# Power_Bank_Circuit.net
KiCad netlist of a schematic drawn in Altium Designer
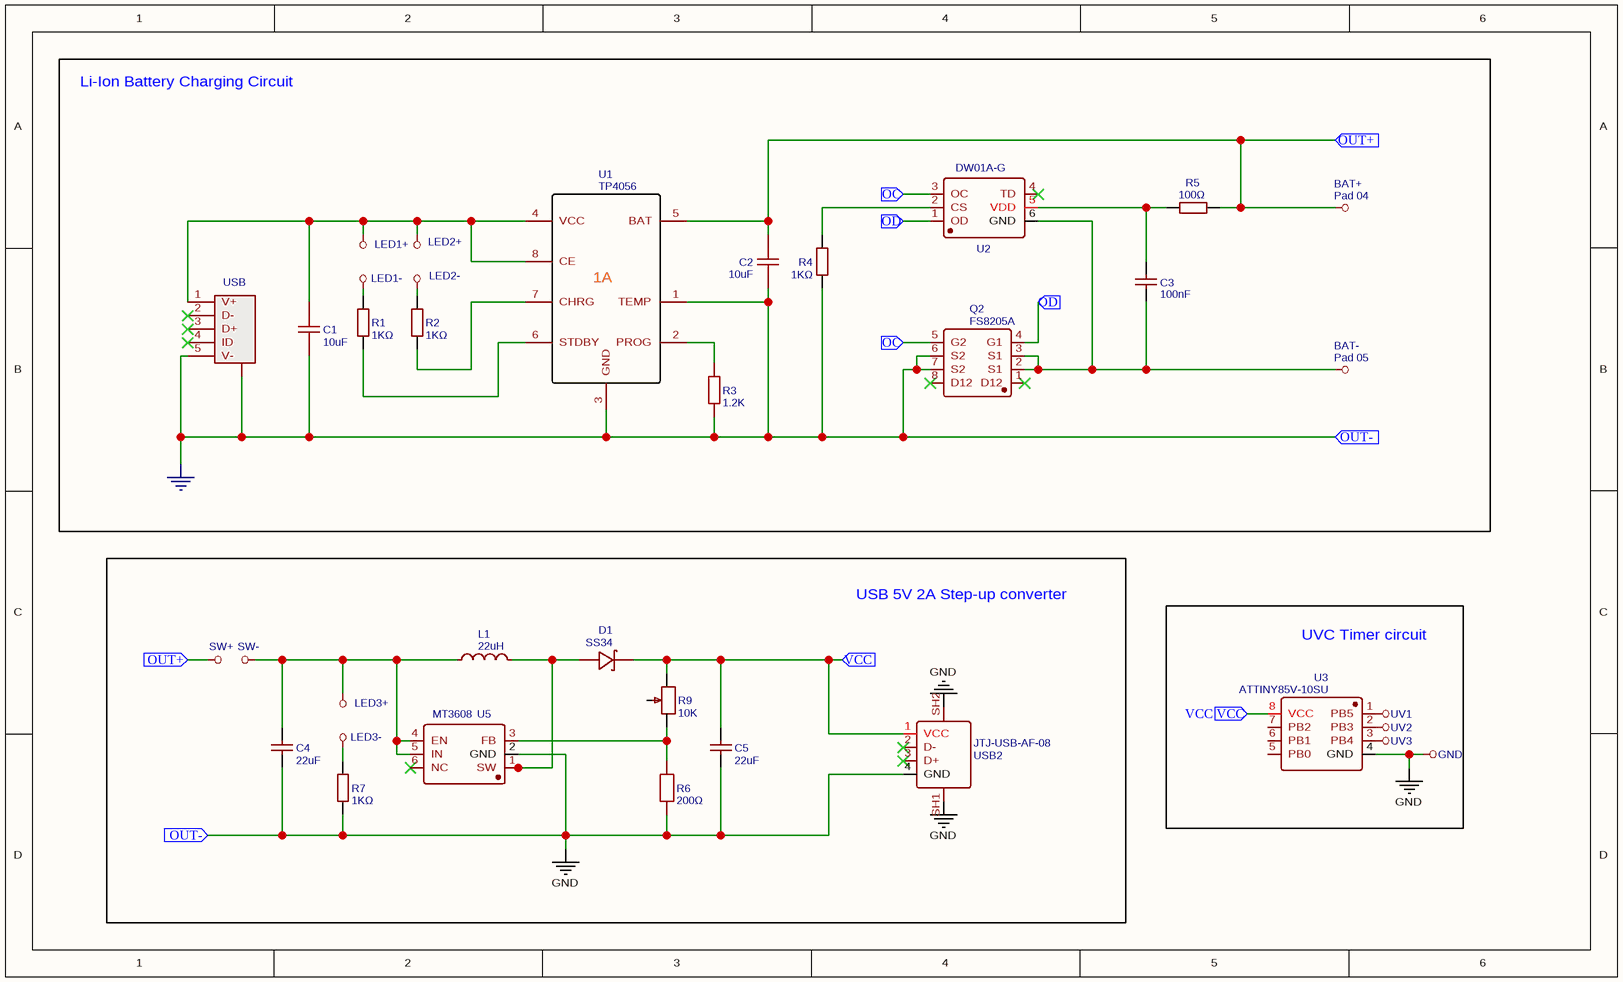
[diagram p0: Power Bank Circuit.schdoc]

(export (version "E")
  (design (tool "Eeschema 10.0.6"))
  (components
    (comp (ref "BAT+")
      (value "Pad 04")
      (fields (field (name "BOM_MANUFACTURER PART") "?") (field (name "CONTRIBUTOR") "DangerousPrototype"))
      (libsource (lib "altium-import") (part "root_3_Pad 04_"))
    )
    (comp (ref "BAT-")
      (value "Pad 05")
      (fields (field (name "BOM_MANUFACTURER PART") "?") (field (name "CONTRIBUTOR") "DangerousPrototype"))
      (libsource (lib "altium-import") (part "root_3_Pad 05_"))
    )
    (comp (ref "C1")
      (value "10uF")
      (fields
        (field (name "BOM_MANUFACTURER PART") "CL10A106MA8NRNC")
        (field (name "BOM_SUPPLIER PART") "C96446")
      )
      (libsource (lib "altium-import") (part "root_1_10uF_"))
    )
    (comp (ref "C2")
      (value "10uF")
      (fields
        (field (name "BOM_MANUFACTURER PART") "CL10A106MA8NRNC")
        (field (name "BOM_SUPPLIER PART") "C96446")
      )
      (libsource (lib "") (part "root_1_10uF__1"))
    )
    (comp (ref "C3")
      (value "100nF")
      (fields
        (field (name "BOM_MANUFACTURER PART") "CL05B104KO5NNNC")
        (field (name "BOM_SUPPLIER PART") "C1525")
      )
      (libsource (lib "altium-import") (part "root_1_100nF_"))
    )
    (comp (ref "C4")
      (value "22uF")
      (fields
        (field (name "BOM_MANUFACTURER PART") "GRM21BR60J226ME39L")
        (field (name "BOM_SUPPLIER PART") "C77071")
      )
      (libsource (lib "altium-import") (part "root_1_22uF_"))
    )
    (comp (ref "C5")
      (value "22uF")
      (fields
        (field (name "BOM_MANUFACTURER PART") "GRM21BR60J226ME39L")
        (field (name "BOM_SUPPLIER PART") "C77071")
      )
      (libsource (lib "altium-import") (part "root_3_22uF_"))
    )
    (comp (ref "D1")
      (value "SS34")
      (fields (field (name "BOM_SUPPLIER PART") "C266556") (field (name "CONTRIBUTOR") "LCSC"))
      (libsource (lib "altium-import") (part "root_0_SS34_"))
    )
    (comp (ref "GND")
      (value "Pad 05")
      (fields (field (name "BOM_MANUFACTURER PART") "?") (field (name "CONTRIBUTOR") "DangerousPrototype"))
      (libsource (lib "altium-import") (part "root_3_Pad 05_"))
    )
    (comp (ref "L1")
      (value "22uH")
      (fields
        (field (name "BOM_SUPPLIER PART") "C334097")
        (field (name "BOM_MANUFACTURER PART") "JSHC0650H-220M-G")
        (field (name "CONTRIBUTOR") "LCSC")
      )
      (libsource (lib "altium-import") (part "root_0_22uH_"))
    )
    (comp (ref "LED1+")
      (value "Pad 05")
      (fields (field (name "BOM_MANUFACTURER PART") "?") (field (name "CONTRIBUTOR") "DangerousPrototype"))
      (libsource (lib "altium-import") (part "root_0_Pad 05_"))
    )
    (comp (ref "LED1-")
      (value "Pad 05")
      (fields (field (name "BOM_MANUFACTURER PART") "?") (field (name "CONTRIBUTOR") "DangerousPrototype"))
      (libsource (lib "altium-import") (part "root_2_Pad 05_"))
    )
    (comp (ref "LED2+")
      (value "Pad 05")
      (fields (field (name "BOM_MANUFACTURER PART") "?") (field (name "CONTRIBUTOR") "DangerousPrototype"))
      (libsource (lib "altium-import") (part "root_0_Pad 05_"))
    )
    (comp (ref "LED2-")
      (value "Pad 05")
      (fields (field (name "BOM_MANUFACTURER PART") "?") (field (name "CONTRIBUTOR") "DangerousPrototype"))
      (libsource (lib "altium-import") (part "root_2_Pad 05_"))
    )
    (comp (ref "LED3+")
      (value "Pad 05")
      (fields (field (name "BOM_MANUFACTURER PART") "?") (field (name "CONTRIBUTOR") "DangerousPrototype"))
      (libsource (lib "altium-import") (part "root_0_Pad 05_"))
    )
    (comp (ref "LED3-")
      (value "Pad 05")
      (fields (field (name "BOM_MANUFACTURER PART") "?") (field (name "CONTRIBUTOR") "DangerousPrototype"))
      (libsource (lib "altium-import") (part "root_2_Pad 05_"))
    )
    (comp (ref "Q2")
      (value "FS8205A")
      (fields (field (name "BOM_SUPPLIER PART") "C16052"))
      (libsource (lib "altium-import") (part "root_2_FS8205A_"))
    )
    (comp (ref "R1")
      (value "1KΩ")
      (fields
        (field (name "BOM_MANUFACTURER PART") "0402WGF1001TCE")
        (field (name "BOM_SUPPLIER PART") "C11702")
      )
      (libsource (lib "altium-import") (part "root_1_1KΩ_"))
    )
    (comp (ref "R2")
      (value "1KΩ")
      (fields
        (field (name "BOM_MANUFACTURER PART") "0402WGF1001TCE")
        (field (name "BOM_SUPPLIER PART") "C11702")
      )
      (libsource (lib "altium-import") (part "root_1_1KΩ_"))
    )
    (comp (ref "R3")
      (value "1.2K")
      (fields
        (field (name "BOM_SUPPLIER PART") "C203113")
        (field (name "BOM_MANUFACTURER PART") "CR0402-JW-122GLF")
        (field (name "CONTRIBUTOR") "LCSC")
      )
      (libsource (lib "altium-import") (part "root_1_1.2K_"))
    )
    (comp (ref "R4")
      (value "1KΩ")
      (fields
        (field (name "BOM_MANUFACTURER PART") "0402WGF1001TCE")
        (field (name "BOM_SUPPLIER PART") "C11702")
      )
      (libsource (lib "altium-import") (part "root_1_1KΩ_"))
    )
    (comp (ref "R5")
      (value "100Ω")
      (fields
        (field (name "BOM_MANUFACTURER PART") "0603WAF1000T5E")
        (field (name "BOM_SUPPLIER PART") "C22775")
      )
      (libsource (lib "altium-import") (part "root_0_100Ω_"))
    )
    (comp (ref "R6")
      (value "200Ω")
      (fields
        (field (name "BOM_SUPPLIER PART") "C517534")
        (field (name "BOM_MANUFACTURER PART") "TC0625B2000T5K")
        (field (name "CONTRIBUTOR") "LCSC")
      )
      (libsource (lib "altium-import") (part "root_1_200Ω_"))
    )
    (comp (ref "R7")
      (value "1KΩ")
      (fields
        (field (name "BOM_MANUFACTURER PART") "0402WGF1001TCE")
        (field (name "BOM_SUPPLIER PART") "C11702")
      )
      (libsource (lib "altium-import") (part "root_1_1KΩ_"))
    )
    (comp (ref "R9")
      (value "10K")
      (fields
        (field (name "BOM_MANUFACTURER PART") "3296W-1-103LF")
        (field (name "BOM_SUPPLIER PART") "C34846")
      )
      (libsource (lib "altium-import") (part "root_0_10K_"))
    )
    (comp (ref "SW+")
      (value "Pad 05")
      (fields (field (name "BOM_MANUFACTURER PART") "?") (field (name "CONTRIBUTOR") "DangerousPrototype"))
      (libsource (lib "altium-import") (part "root_1_Pad 05_"))
    )
    (comp (ref "SW-")
      (value "Pad 05")
      (fields (field (name "BOM_MANUFACTURER PART") "?") (field (name "CONTRIBUTOR") "DangerousPrototype"))
      (libsource (lib "") (part "root_3_Pad 05__1"))
    )
    (comp (ref "U1")
      (value "TP4056")
      (fields (field (name "BOM_SUPPLIER PART") "C16581") (field (name "CONTRIBUTOR") "Guest"))
      (libsource (lib "altium-import") (part "root_0_TP4056_"))
    )
    (comp (ref "U2")
      (value "DW01A-G")
      (fields (field (name "BOM_SUPPLIER PART") "C61503") (field (name "CONTRIBUTOR") "LCSC"))
      (libsource (lib "altium-import") (part "root_0_DW01A-G_"))
    )
    (comp (ref "U3")
      (value "ATTINY85V-10SU")
      (fields (field (name "BOM_SUPPLIER PART") "C152192") (field (name "CONTRIBUTOR") "LCSC"))
      (libsource (lib "altium-import") (part "root_0_ATTINY85V-10SU_"))
    )
    (comp (ref "U5")
      (value "MT3608")
      (fields (field (name "BOM_SUPPLIER PART") "C84817"))
      (libsource (lib "altium-import") (part "root_0_MT3608_"))
    )
    (comp (ref "USB")
      (value "micro 5PBoard5.9No column plus welding feet")
      (fields (field (name "BOM_SUPPLIER PART") "C40955"))
      (libsource (lib "altium-import") (part "root_0_micro 5PBoard5.9No column plus welding feet_"))
    )
    (comp (ref "USB2")
      (value "JTJ-USB-AF-08")
      (fields (field (name "BOM_SUPPLIER PART") "C2345") (field (name "CONTRIBUTOR") "LCSC"))
      (libsource (lib "altium-import") (part "root_2_JTJ-USB-AF-08_"))
    )
    (comp (ref "UV1")
      (value "Pad 05")
      (fields (field (name "BOM_MANUFACTURER PART") "?") (field (name "CONTRIBUTOR") "DangerousPrototype"))
      (libsource (lib "altium-import") (part "root_3_Pad 05_"))
    )
    (comp (ref "UV2")
      (value "Pad 05")
      (fields (field (name "BOM_MANUFACTURER PART") "?") (field (name "CONTRIBUTOR") "DangerousPrototype"))
      (libsource (lib "altium-import") (part "root_3_Pad 05_"))
    )
    (comp (ref "UV3")
      (value "Pad 05")
      (fields (field (name "BOM_MANUFACTURER PART") "?") (field (name "CONTRIBUTOR") "DangerousPrototype"))
      (libsource (lib "altium-import") (part "root_3_Pad 05_"))
    )
  )
  (nets
    (net (code "1") (name "/OC") (class "Default")
      (node (ref "Q2") (pin "5") (pinfunction "G2_5") (pintype "passive"))
      (node (ref "U2") (pin "3") (pinfunction "OC_3") (pintype "passive"))
    )
    (net (code "2") (name "/OD") (class "Default")
      (node (ref "Q2") (pin "4") (pinfunction "G1_4") (pintype "passive"))
      (node (ref "U2") (pin "1") (pinfunction "OD_1") (pintype "passive"))
    )
    (net (code "3") (name "/OUT+") (class "Default")
      (node (ref "BAT+") (pin "P") (pinfunction "P_P") (pintype "passive"))
      (node (ref "C2") (pin "2") (pinfunction "2_2") (pintype "passive"))
      (node (ref "R5") (pin "2") (pinfunction "2_2") (pintype "passive"))
      (node (ref "SW+") (pin "P") (pinfunction "P_P") (pintype "passive"))
      (node (ref "U1") (pin "5") (pinfunction "BAT_5") (pintype "passive"))
    )
    (net (code "4") (name "/VCC") (class "Default")
      (node (ref "C5") (pin "1") (pinfunction "1_1") (pintype "passive"))
      (node (ref "D1") (pin "1") (pinfunction "C_1") (pintype "passive"))
      (node (ref "R9") (pin "1") (pinfunction "1_1") (pintype "passive"))
      (node (ref "U3") (pin "8") (pinfunction "VCC_8") (pintype "passive"))
      (node (ref "USB2") (pin "1") (pinfunction "VCC_1") (pintype "passive"))
    )
    (net (code "5") (name "GND") (class "Default")
      (node (ref "C1") (pin "1") (pinfunction "1_1") (pintype "passive"))
      (node (ref "C2") (pin "1") (pinfunction "1_1") (pintype "passive"))
      (node (ref "C4") (pin "1") (pinfunction "1_1") (pintype "passive"))
      (node (ref "C5") (pin "2") (pinfunction "2_2") (pintype "passive"))
      (node (ref "GND") (pin "P") (pinfunction "P_P") (pintype "passive"))
      (node (ref "Q2") (pin "6") (pinfunction "S2_6") (pintype "passive"))
      (node (ref "Q2") (pin "7") (pinfunction "S2_7") (pintype "passive"))
      (node (ref "R3") (pin "1") (pinfunction "1_1") (pintype "passive"))
      (node (ref "R4") (pin "1") (pinfunction "1_1") (pintype "passive"))
      (node (ref "R6") (pin "1") (pinfunction "1_1") (pintype "passive"))
      (node (ref "R7") (pin "1") (pinfunction "1_1") (pintype "passive"))
      (node (ref "U1") (pin "1") (pinfunction "TEMP_1") (pintype "passive"))
      (node (ref "U1") (pin "3") (pinfunction "GND_3") (pintype "passive"))
      (node (ref "U3") (pin "4") (pinfunction "GND_4") (pintype "passive"))
      (node (ref "U5") (pin "2") (pinfunction "GND_2") (pintype "passive"))
      (node (ref "USB") (pin "0") (pinfunction "MTN6_0") (pintype "passive"))
      (node (ref "USB") (pin "5") (pinfunction "V-_5") (pintype "passive"))
      (node (ref "USB2") (pin "4") (pinfunction "GND_4") (pintype "passive"))
      (node (ref "USB2") (pin "SH1") (pinfunction "SH1_SH1") (pintype "passive"))
      (node (ref "USB2") (pin "SH2") (pinfunction "SH2_SH2") (pintype "passive"))
    )
    (net (code "6") (name "Net-(D1-A)") (class "Default")
      (node (ref "D1") (pin "2") (pinfunction "A_2") (pintype "passive"))
      (node (ref "L1") (pin "2") (pinfunction "2_2") (pintype "passive"))
      (node (ref "U5") (pin "1") (pinfunction "SW_1") (pintype "passive"))
    )
    (net (code "7") (name "Net-(LED1--PadP)") (class "Default")
      (node (ref "LED1-") (pin "P") (pinfunction "P_P") (pintype "passive"))
      (node (ref "R1") (pin "2") (pinfunction "2_2") (pintype "passive"))
    )
    (net (code "8") (name "Net-(LED2--PadP)") (class "Default")
      (node (ref "LED2-") (pin "P") (pinfunction "P_P") (pintype "passive"))
      (node (ref "R2") (pin "2") (pinfunction "2_2") (pintype "passive"))
    )
    (net (code "9") (name "Net-(LED3--PadP)") (class "Default")
      (node (ref "LED3-") (pin "P") (pinfunction "P_P") (pintype "passive"))
      (node (ref "R7") (pin "2") (pinfunction "2_2") (pintype "passive"))
    )
    (net (code "10") (name "Net-(U1-CE)") (class "Default")
      (node (ref "C1") (pin "2") (pinfunction "2_2") (pintype "passive"))
      (node (ref "LED1+") (pin "P") (pinfunction "P_P") (pintype "passive"))
      (node (ref "LED2+") (pin "P") (pinfunction "P_P") (pintype "passive"))
      (node (ref "U1") (pin "4") (pinfunction "VCC_4") (pintype "passive"))
      (node (ref "U1") (pin "8") (pinfunction "CE_8") (pintype "passive"))
      (node (ref "USB") (pin "1") (pinfunction "V+_1") (pintype "passive"))
    )
    (net (code "11") (name "Net-(U1-CHRG)") (class "Default")
      (node (ref "R2") (pin "1") (pinfunction "1_1") (pintype "passive"))
      (node (ref "U1") (pin "7") (pinfunction "CHRG_7") (pintype "passive"))
    )
    (net (code "12") (name "Net-(U1-PROG)") (class "Default")
      (node (ref "R3") (pin "2") (pinfunction "2_2") (pintype "passive"))
      (node (ref "U1") (pin "2") (pinfunction "PROG_2") (pintype "passive"))
    )
    (net (code "13") (name "Net-(U1-STDBY)") (class "Default")
      (node (ref "R1") (pin "1") (pinfunction "1_1") (pintype "passive"))
      (node (ref "U1") (pin "6") (pinfunction "STDBY_6") (pintype "passive"))
    )
    (net (code "14") (name "Net-(U2-CS)") (class "Default")
      (node (ref "R4") (pin "2") (pinfunction "2_2") (pintype "passive"))
      (node (ref "U2") (pin "2") (pinfunction "CS_2") (pintype "passive"))
    )
    (net (code "15") (name "Net-(U2-GND)") (class "Default")
      (node (ref "BAT-") (pin "P") (pinfunction "P_P") (pintype "passive"))
      (node (ref "C3") (pin "1") (pinfunction "1_1") (pintype "passive"))
      (node (ref "Q2") (pin "2") (pinfunction "S1_2") (pintype "passive"))
      (node (ref "Q2") (pin "3") (pinfunction "S1_3") (pintype "passive"))
      (node (ref "U2") (pin "6") (pinfunction "GND_6") (pintype "passive"))
    )
    (net (code "16") (name "Net-(U2-VDD)") (class "Default")
      (node (ref "C3") (pin "2") (pinfunction "2_2") (pintype "passive"))
      (node (ref "R5") (pin "1") (pinfunction "1_1") (pintype "passive"))
      (node (ref "U2") (pin "5") (pinfunction "VDD_5") (pintype "passive"))
    )
    (net (code "17") (name "Net-(U3-PB3)") (class "Default")
      (node (ref "U3") (pin "2") (pinfunction "PB3_2") (pintype "passive"))
      (node (ref "UV2") (pin "P") (pinfunction "P_P") (pintype "passive"))
    )
    (net (code "18") (name "Net-(U3-PB4)") (class "Default")
      (node (ref "U3") (pin "3") (pinfunction "PB4_3") (pintype "passive"))
      (node (ref "UV3") (pin "P") (pinfunction "P_P") (pintype "passive"))
    )
    (net (code "19") (name "Net-(U3-PB5)") (class "Default")
      (node (ref "U3") (pin "1") (pinfunction "PB5_1") (pintype "passive"))
      (node (ref "UV1") (pin "P") (pinfunction "P_P") (pintype "passive"))
    )
    (net (code "20") (name "Net-(U5-EN)") (class "Default")
      (node (ref "C4") (pin "2") (pinfunction "2_2") (pintype "passive"))
      (node (ref "L1") (pin "1") (pinfunction "1_1") (pintype "passive"))
      (node (ref "LED3+") (pin "P") (pinfunction "P_P") (pintype "passive"))
      (node (ref "SW-") (pin "P") (pinfunction "P_P") (pintype "passive"))
      (node (ref "U5") (pin "4") (pinfunction "EN_4") (pintype "passive"))
      (node (ref "U5") (pin "5") (pinfunction "IN_5") (pintype "passive"))
    )
    (net (code "21") (name "Net-(U5-FB)") (class "Default")
      (node (ref "R6") (pin "2") (pinfunction "2_2") (pintype "passive"))
      (node (ref "R9") (pin "3") (pinfunction "3_3") (pintype "passive"))
      (node (ref "U5") (pin "3") (pinfunction "FB_3") (pintype "passive"))
    )
    (net (code "22") (name "unconnected-(Q2-D12-Pad1)") (class "Default")
      (node (ref "Q2") (pin "1") (pinfunction "D12_1") (pintype "passive+no_connect"))
    )
    (net (code "23") (name "unconnected-(Q2-D12-Pad8)") (class "Default")
      (node (ref "Q2") (pin "8") (pinfunction "D12_8") (pintype "passive+no_connect"))
    )
    (net (code "24") (name "unconnected-(R9-Pad2)") (class "Default")
      (node (ref "R9") (pin "2") (pinfunction "2_2") (pintype "passive"))
    )
    (net (code "25") (name "unconnected-(U2-TD-Pad4)") (class "Default")
      (node (ref "U2") (pin "4") (pinfunction "TD_4") (pintype "passive+no_connect"))
    )
    (net (code "26") (name "unconnected-(U3-PB0-Pad5)") (class "Default")
      (node (ref "U3") (pin "5") (pinfunction "PB0_5") (pintype "passive"))
    )
    (net (code "27") (name "unconnected-(U3-PB1-Pad6)") (class "Default")
      (node (ref "U3") (pin "6") (pinfunction "PB1_6") (pintype "passive"))
    )
    (net (code "28") (name "unconnected-(U3-PB2-Pad7)") (class "Default")
      (node (ref "U3") (pin "7") (pinfunction "PB2_7") (pintype "passive"))
    )
    (net (code "29") (name "unconnected-(U5-NC-Pad6)") (class "Default")
      (node (ref "U5") (pin "6") (pinfunction "NC_6") (pintype "passive+no_connect"))
    )
    (net (code "30") (name "unconnected-(USB-D+-Pad3)") (class "Default")
      (node (ref "USB") (pin "3") (pinfunction "D+_3") (pintype "passive+no_connect"))
    )
    (net (code "31") (name "unconnected-(USB-D--Pad2)") (class "Default")
      (node (ref "USB") (pin "2") (pinfunction "D-_2") (pintype "passive+no_connect"))
    )
    (net (code "32") (name "unconnected-(USB-ID-Pad4)") (class "Default")
      (node (ref "USB") (pin "4") (pinfunction "ID_4") (pintype "passive+no_connect"))
    )
    (net (code "33") (name "unconnected-(USB2-D+-Pad3)") (class "Default")
      (node (ref "USB2") (pin "3") (pinfunction "D+_3") (pintype "passive+no_connect"))
    )
    (net (code "34") (name "unconnected-(USB2-D--Pad2)") (class "Default")
      (node (ref "USB2") (pin "2") (pinfunction "D-_2") (pintype "passive+no_connect"))
    )
  )
)
